# ProPrj_EasyHub_r2.net
KiCad netlist of a schematic drawn in EasyEDA Pro
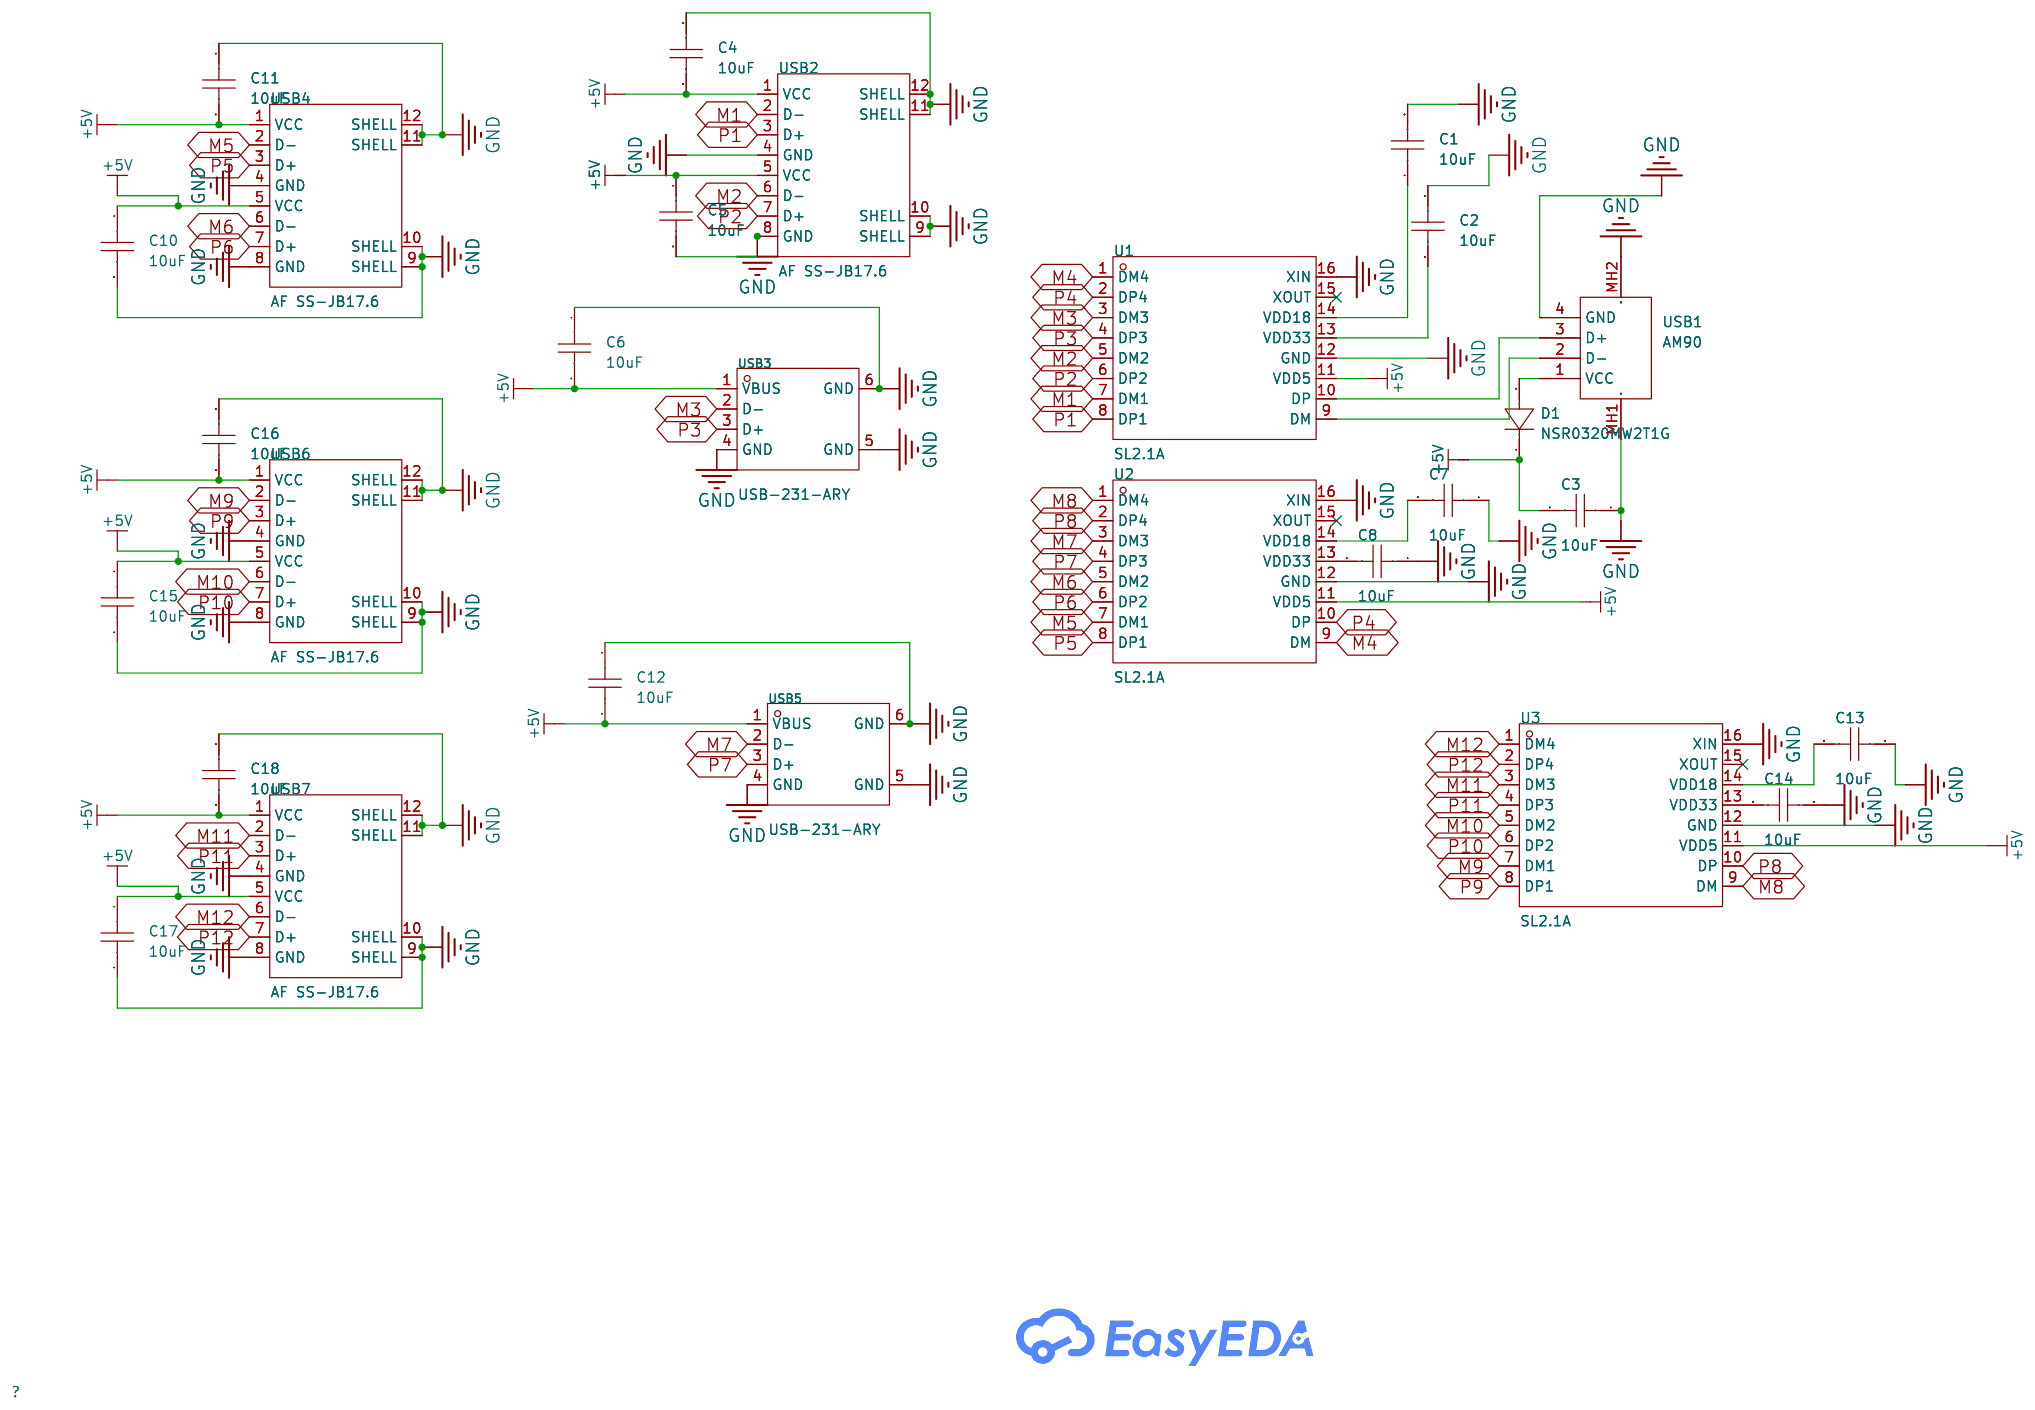
[diagram p0: schematic sheet]

(export (version "E")
  (design (tool "Eeschema 10.0.6"))
  (components
    (comp (ref "C1")
      (value "10uF")
      (footprint "easyedapro:C0603")
      (description "Capacitance:10uF Tolerance:±10% Tolerance:±10% Voltage Rating:10V Temperature Coefficient:X5R")
      (fields
        (field (name "Manufacturer Part") "CL10A106KP8NNNC")
        (field (name "Manufacturer") "SAMSUNG(三星)")
      )
      (libsource (lib "easyedapro") (part "CAP"))
    )
    (comp (ref "C2")
      (value "10uF")
      (footprint "easyedapro:C0603")
      (description "Capacitance:10uF Tolerance:±10% Tolerance:±10% Voltage Rating:10V Temperature Coefficient:X5R")
      (fields
        (field (name "Manufacturer Part") "CL10A106KP8NNNC")
        (field (name "Manufacturer") "SAMSUNG(三星)")
      )
      (libsource (lib "easyedapro") (part "CAP"))
    )
    (comp (ref "C3")
      (value "10uF")
      (footprint "easyedapro:C0603")
      (description "Capacitance:10uF Tolerance:±10% Tolerance:±10% Voltage Rating:10V Temperature Coefficient:X5R")
      (fields
        (field (name "Manufacturer Part") "CL10A106KP8NNNC")
        (field (name "Manufacturer") "SAMSUNG(三星)")
      )
      (libsource (lib "easyedapro") (part "CAP"))
    )
    (comp (ref "C4")
      (value "10uF")
      (footprint "easyedapro:C0603")
      (description "Capacitance:10uF Tolerance:±10% Tolerance:±10% Voltage Rating:10V Temperature Coefficient:X5R")
      (fields
        (field (name "Manufacturer Part") "CL10A106KP8NNNC")
        (field (name "Manufacturer") "SAMSUNG(三星)")
      )
      (libsource (lib "easyedapro") (part "CAP"))
    )
    (comp (ref "C5")
      (value "10uF")
      (footprint "easyedapro:C0603")
      (description "Capacitance:10uF Tolerance:±10% Tolerance:±10% Voltage Rating:10V Temperature Coefficient:X5R")
      (fields
        (field (name "Manufacturer Part") "CL10A106KP8NNNC")
        (field (name "Manufacturer") "SAMSUNG(三星)")
      )
      (libsource (lib "easyedapro") (part "CAP"))
    )
    (comp (ref "C6")
      (value "10uF")
      (footprint "easyedapro:C0603")
      (description "Capacitance:10uF Tolerance:±10% Tolerance:±10% Voltage Rating:10V Temperature Coefficient:X5R")
      (fields
        (field (name "Manufacturer Part") "CL10A106KP8NNNC")
        (field (name "Manufacturer") "SAMSUNG(三星)")
      )
      (libsource (lib "easyedapro") (part "CAP"))
    )
    (comp (ref "C7")
      (value "10uF")
      (footprint "easyedapro:C0603")
      (description "Capacitance:10uF Tolerance:±10% Tolerance:±10% Voltage Rating:10V Temperature Coefficient:X5R")
      (fields
        (field (name "Manufacturer Part") "CL10A106KP8NNNC")
        (field (name "Manufacturer") "SAMSUNG(三星)")
      )
      (libsource (lib "easyedapro") (part "CAP"))
    )
    (comp (ref "C8")
      (value "10uF")
      (footprint "easyedapro:C0603")
      (description "Capacitance:10uF Tolerance:±10% Tolerance:±10% Voltage Rating:10V Temperature Coefficient:X5R")
      (fields
        (field (name "Manufacturer Part") "CL10A106KP8NNNC")
        (field (name "Manufacturer") "SAMSUNG(三星)")
      )
      (libsource (lib "easyedapro") (part "CAP"))
    )
    (comp (ref "C10")
      (value "10uF")
      (footprint "easyedapro:C0603")
      (description "Capacitance:10uF Tolerance:±10% Tolerance:±10% Voltage Rating:10V Temperature Coefficient:X5R")
      (fields
        (field (name "Manufacturer Part") "CL10A106KP8NNNC")
        (field (name "Manufacturer") "SAMSUNG(三星)")
      )
      (libsource (lib "easyedapro") (part "CAP"))
    )
    (comp (ref "C11")
      (value "10uF")
      (footprint "easyedapro:C0603")
      (description "Capacitance:10uF Tolerance:±10% Tolerance:±10% Voltage Rating:10V Temperature Coefficient:X5R")
      (fields
        (field (name "Manufacturer Part") "CL10A106KP8NNNC")
        (field (name "Manufacturer") "SAMSUNG(三星)")
      )
      (libsource (lib "easyedapro") (part "CAP"))
    )
    (comp (ref "C12")
      (value "10uF")
      (footprint "easyedapro:C0603")
      (description "Capacitance:10uF Tolerance:±10% Tolerance:±10% Voltage Rating:10V Temperature Coefficient:X5R")
      (fields
        (field (name "Manufacturer Part") "CL10A106KP8NNNC")
        (field (name "Manufacturer") "SAMSUNG(三星)")
      )
      (libsource (lib "easyedapro") (part "CAP"))
    )
    (comp (ref "C13")
      (value "10uF")
      (footprint "easyedapro:C0603")
      (description "Capacitance:10uF Tolerance:±10% Tolerance:±10% Voltage Rating:10V Temperature Coefficient:X5R")
      (fields
        (field (name "Manufacturer Part") "CL10A106KP8NNNC")
        (field (name "Manufacturer") "SAMSUNG(三星)")
      )
      (libsource (lib "easyedapro") (part "CAP"))
    )
    (comp (ref "C14")
      (value "10uF")
      (footprint "easyedapro:C0603")
      (description "Capacitance:10uF Tolerance:±10% Tolerance:±10% Voltage Rating:10V Temperature Coefficient:X5R")
      (fields
        (field (name "Manufacturer Part") "CL10A106KP8NNNC")
        (field (name "Manufacturer") "SAMSUNG(三星)")
      )
      (libsource (lib "easyedapro") (part "CAP"))
    )
    (comp (ref "C15")
      (value "10uF")
      (footprint "easyedapro:C0603")
      (description "Capacitance:10uF Tolerance:±10% Tolerance:±10% Voltage Rating:10V Temperature Coefficient:X5R")
      (fields
        (field (name "Manufacturer Part") "CL10A106KP8NNNC")
        (field (name "Manufacturer") "SAMSUNG(三星)")
      )
      (libsource (lib "easyedapro") (part "CAP"))
    )
    (comp (ref "C16")
      (value "10uF")
      (footprint "easyedapro:C0603")
      (description "Capacitance:10uF Tolerance:±10% Tolerance:±10% Voltage Rating:10V Temperature Coefficient:X5R")
      (fields
        (field (name "Manufacturer Part") "CL10A106KP8NNNC")
        (field (name "Manufacturer") "SAMSUNG(三星)")
      )
      (libsource (lib "easyedapro") (part "CAP"))
    )
    (comp (ref "C17")
      (value "10uF")
      (footprint "easyedapro:C0603")
      (description "Capacitance:10uF Tolerance:±10% Tolerance:±10% Voltage Rating:10V Temperature Coefficient:X5R")
      (fields
        (field (name "Manufacturer Part") "CL10A106KP8NNNC")
        (field (name "Manufacturer") "SAMSUNG(三星)")
      )
      (libsource (lib "easyedapro") (part "CAP"))
    )
    (comp (ref "C18")
      (value "10uF")
      (footprint "easyedapro:C0603")
      (description "Capacitance:10uF Tolerance:±10% Tolerance:±10% Voltage Rating:10V Temperature Coefficient:X5R")
      (fields
        (field (name "Manufacturer Part") "CL10A106KP8NNNC")
        (field (name "Manufacturer") "SAMSUNG(三星)")
      )
      (libsource (lib "easyedapro") (part "CAP"))
    )
    (comp (ref "D1")
      (value "NSR0320MW2T1G")
      (footprint "easyedapro:SMA_L4.4-W2.8-LS5.4-RD")
      (fields (field (name "Manufacturer") "onsemi(安森美)"))
      (libsource (lib "easyedapro") (part "D_1N4007"))
    )
    (comp (ref "U1")
      (value "SL2.1A")
      (footprint "easyedapro:SOP-16_L10.0-W3.9-P1.27-LS6.0-BL")
      (fields (field (name "Manufacturer") "CoreChips(和芯润德)"))
      (libsource (lib "easyedapro") (part "SL2.1A_C6798314"))
    )
    (comp (ref "U2")
      (value "SL2.1A")
      (footprint "easyedapro:SOP-16_L10.0-W3.9-P1.27-LS6.0-BL")
      (fields (field (name "Manufacturer") "CoreChips(和芯润德)"))
      (libsource (lib "easyedapro") (part "SL2.1A_C6798314"))
    )
    (comp (ref "U3")
      (value "SL2.1A")
      (footprint "easyedapro:SOP-16_L10.0-W3.9-P1.27-LS6.0-BL")
      (fields (field (name "Manufacturer") "CoreChips(和芯润德)"))
      (libsource (lib "easyedapro") (part "SL2.1A_C6798314"))
    )
    (comp (ref "USB1")
      (value "AM90")
      (footprint "easyedapro:USB-AM-TH_AM90")
      (fields (field (name "Manufacturer") "SHOU HAN(首韩)"))
      (libsource (lib "easyedapro") (part "AM90"))
    )
    (comp (ref "USB2")
      (value "AF SS-JB17.6")
      (footprint "easyedapro:USB-A-TH_AF-SS-JB17.6")
      (fields (field (name "Manufacturer") "SHOU HAN(首韩)"))
      (libsource (lib "easyedapro") (part "AF SS-JB17.6"))
    )
    (comp (ref "USB3")
      (value "USB-231-ARY")
      (footprint "easyedapro:USB-A-TH_USB-231-ARY")
      (fields (field (name "Manufacturer") "XUNPU(讯普)"))
      (libsource (lib "easyedapro") (part "USB-231-ARY"))
    )
    (comp (ref "USB4")
      (value "AF SS-JB17.6")
      (footprint "easyedapro:USB-A-TH_AF-SS-JB17.6")
      (fields (field (name "Manufacturer") "SHOU HAN(首韩)"))
      (libsource (lib "easyedapro") (part "AF SS-JB17.6"))
    )
    (comp (ref "USB5")
      (value "USB-231-ARY")
      (footprint "easyedapro:USB-A-TH_USB-231-ARY")
      (fields (field (name "Manufacturer") "XUNPU(讯普)"))
      (libsource (lib "easyedapro") (part "USB-231-ARY"))
    )
    (comp (ref "USB6")
      (value "AF SS-JB17.6")
      (footprint "easyedapro:USB-A-TH_AF-SS-JB17.6")
      (fields (field (name "Manufacturer") "SHOU HAN(首韩)"))
      (libsource (lib "easyedapro") (part "AF SS-JB17.6"))
    )
    (comp (ref "USB7")
      (value "AF SS-JB17.6")
      (footprint "easyedapro:USB-A-TH_AF-SS-JB17.6")
      (fields (field (name "Manufacturer") "SHOU HAN(首韩)"))
      (libsource (lib "easyedapro") (part "AF SS-JB17.6"))
    )
  )
  (nets
    (net (code "1") (name "+5V") (class "Default")
      (node (ref "C10") (pin "1") (pinfunction "1_1") (pintype "input"))
      (node (ref "C11") (pin "2") (pinfunction "2_2") (pintype "input"))
      (node (ref "C12") (pin "2") (pinfunction "2_2") (pintype "input"))
      (node (ref "C15") (pin "1") (pinfunction "1_1") (pintype "input"))
      (node (ref "C16") (pin "2") (pinfunction "2_2") (pintype "input"))
      (node (ref "C17") (pin "1") (pinfunction "1_1") (pintype "input"))
      (node (ref "C18") (pin "2") (pinfunction "2_2") (pintype "input"))
      (node (ref "C3") (pin "2") (pinfunction "2_2") (pintype "input"))
      (node (ref "C4") (pin "2") (pinfunction "2_2") (pintype "input"))
      (node (ref "C5") (pin "1") (pinfunction "1_1") (pintype "input"))
      (node (ref "C6") (pin "2") (pinfunction "2_2") (pintype "input"))
      (node (ref "D1") (pin "1") (pinfunction "K_1") (pintype "input"))
      (node (ref "U1") (pin "11") (pinfunction "VDD5_11") (pintype "unspecified"))
      (node (ref "U2") (pin "11") (pinfunction "VDD5_11") (pintype "unspecified"))
      (node (ref "U3") (pin "11") (pinfunction "VDD5_11") (pintype "unspecified"))
      (node (ref "USB2") (pin "1") (pinfunction "VCC_1") (pintype "unspecified"))
      (node (ref "USB2") (pin "5") (pinfunction "VCC_5") (pintype "unspecified"))
      (node (ref "USB3") (pin "1") (pinfunction "VBUS_1") (pintype "input"))
      (node (ref "USB4") (pin "1") (pinfunction "VCC_1") (pintype "unspecified"))
      (node (ref "USB4") (pin "5") (pinfunction "VCC_5") (pintype "unspecified"))
      (node (ref "USB5") (pin "1") (pinfunction "VBUS_1") (pintype "input"))
      (node (ref "USB6") (pin "1") (pinfunction "VCC_1") (pintype "unspecified"))
      (node (ref "USB6") (pin "5") (pinfunction "VCC_5") (pintype "unspecified"))
      (node (ref "USB7") (pin "1") (pinfunction "VCC_1") (pintype "unspecified"))
      (node (ref "USB7") (pin "5") (pinfunction "VCC_5") (pintype "unspecified"))
    )
    (net (code "2") (name "GND") (class "Default")
      (node (ref "C1") (pin "2") (pinfunction "2_2") (pintype "input"))
      (node (ref "C10") (pin "2") (pinfunction "2_2") (pintype "input"))
      (node (ref "C11") (pin "1") (pinfunction "1_1") (pintype "input"))
      (node (ref "C12") (pin "1") (pinfunction "1_1") (pintype "input"))
      (node (ref "C13") (pin "1") (pinfunction "1_1") (pintype "input"))
      (node (ref "C14") (pin "1") (pinfunction "1_1") (pintype "input"))
      (node (ref "C15") (pin "2") (pinfunction "2_2") (pintype "input"))
      (node (ref "C16") (pin "1") (pinfunction "1_1") (pintype "input"))
      (node (ref "C17") (pin "2") (pinfunction "2_2") (pintype "input"))
      (node (ref "C18") (pin "1") (pinfunction "1_1") (pintype "input"))
      (node (ref "C2") (pin "1") (pinfunction "1_1") (pintype "input"))
      (node (ref "C3") (pin "1") (pinfunction "1_1") (pintype "input"))
      (node (ref "C4") (pin "1") (pinfunction "1_1") (pintype "input"))
      (node (ref "C5") (pin "2") (pinfunction "2_2") (pintype "input"))
      (node (ref "C6") (pin "1") (pinfunction "1_1") (pintype "input"))
      (node (ref "C7") (pin "1") (pinfunction "1_1") (pintype "input"))
      (node (ref "C8") (pin "1") (pinfunction "1_1") (pintype "input"))
      (node (ref "U1") (pin "12") (pinfunction "GND_12") (pintype "unspecified"))
      (node (ref "U1") (pin "16") (pinfunction "XIN_16") (pintype "unspecified"))
      (node (ref "U2") (pin "12") (pinfunction "GND_12") (pintype "unspecified"))
      (node (ref "U2") (pin "16") (pinfunction "XIN_16") (pintype "unspecified"))
      (node (ref "U3") (pin "12") (pinfunction "GND_12") (pintype "unspecified"))
      (node (ref "U3") (pin "16") (pinfunction "XIN_16") (pintype "unspecified"))
      (node (ref "USB1") (pin "4") (pinfunction "GND_4") (pintype "input"))
      (node (ref "USB1") (pin "MH1") (pinfunction "MH1_MH1") (pintype "unspecified"))
      (node (ref "USB1") (pin "MH2") (pinfunction "MH2_MH2") (pintype "unspecified"))
      (node (ref "USB2") (pin "10") (pinfunction "SHELL_10") (pintype "unspecified"))
      (node (ref "USB2") (pin "11") (pinfunction "SHELL_11") (pintype "unspecified"))
      (node (ref "USB2") (pin "12") (pinfunction "SHELL_12") (pintype "unspecified"))
      (node (ref "USB2") (pin "4") (pinfunction "GND_4") (pintype "unspecified"))
      (node (ref "USB2") (pin "8") (pinfunction "GND_8") (pintype "unspecified"))
      (node (ref "USB2") (pin "9") (pinfunction "SHELL_9") (pintype "unspecified"))
      (node (ref "USB3") (pin "4") (pinfunction "GND_4") (pintype "input"))
      (node (ref "USB3") (pin "5") (pinfunction "GND_5") (pintype "input"))
      (node (ref "USB3") (pin "6") (pinfunction "GND_6") (pintype "input"))
      (node (ref "USB4") (pin "10") (pinfunction "SHELL_10") (pintype "unspecified"))
      (node (ref "USB4") (pin "11") (pinfunction "SHELL_11") (pintype "unspecified"))
      (node (ref "USB4") (pin "12") (pinfunction "SHELL_12") (pintype "unspecified"))
      (node (ref "USB4") (pin "4") (pinfunction "GND_4") (pintype "unspecified"))
      (node (ref "USB4") (pin "8") (pinfunction "GND_8") (pintype "unspecified"))
      (node (ref "USB4") (pin "9") (pinfunction "SHELL_9") (pintype "unspecified"))
      (node (ref "USB5") (pin "4") (pinfunction "GND_4") (pintype "input"))
      (node (ref "USB5") (pin "5") (pinfunction "GND_5") (pintype "input"))
      (node (ref "USB5") (pin "6") (pinfunction "GND_6") (pintype "input"))
      (node (ref "USB6") (pin "10") (pinfunction "SHELL_10") (pintype "unspecified"))
      (node (ref "USB6") (pin "11") (pinfunction "SHELL_11") (pintype "unspecified"))
      (node (ref "USB6") (pin "12") (pinfunction "SHELL_12") (pintype "unspecified"))
      (node (ref "USB6") (pin "4") (pinfunction "GND_4") (pintype "unspecified"))
      (node (ref "USB6") (pin "8") (pinfunction "GND_8") (pintype "unspecified"))
      (node (ref "USB6") (pin "9") (pinfunction "SHELL_9") (pintype "unspecified"))
      (node (ref "USB7") (pin "10") (pinfunction "SHELL_10") (pintype "unspecified"))
      (node (ref "USB7") (pin "11") (pinfunction "SHELL_11") (pintype "unspecified"))
      (node (ref "USB7") (pin "12") (pinfunction "SHELL_12") (pintype "unspecified"))
      (node (ref "USB7") (pin "4") (pinfunction "GND_4") (pintype "unspecified"))
      (node (ref "USB7") (pin "8") (pinfunction "GND_8") (pintype "unspecified"))
      (node (ref "USB7") (pin "9") (pinfunction "SHELL_9") (pintype "unspecified"))
    )
    (net (code "3") (name "M1") (class "Default")
      (node (ref "U1") (pin "7") (pinfunction "DM1_7") (pintype "unspecified"))
      (node (ref "USB2") (pin "2") (pinfunction "D-_2") (pintype "unspecified"))
    )
    (net (code "4") (name "M2") (class "Default")
      (node (ref "U1") (pin "5") (pinfunction "DM2_5") (pintype "unspecified"))
      (node (ref "USB2") (pin "6") (pinfunction "D-_6") (pintype "unspecified"))
    )
    (net (code "5") (name "M3") (class "Default")
      (node (ref "U1") (pin "3") (pinfunction "DM3_3") (pintype "unspecified"))
      (node (ref "USB3") (pin "2") (pinfunction "D-_2") (pintype "input"))
    )
    (net (code "6") (name "M4") (class "Default")
      (node (ref "U1") (pin "1") (pinfunction "DM4_1") (pintype "unspecified"))
      (node (ref "U2") (pin "9") (pinfunction "DM_9") (pintype "unspecified"))
    )
    (net (code "7") (name "M5") (class "Default")
      (node (ref "U2") (pin "7") (pinfunction "DM1_7") (pintype "unspecified"))
      (node (ref "USB4") (pin "2") (pinfunction "D-_2") (pintype "unspecified"))
    )
    (net (code "8") (name "M6") (class "Default")
      (node (ref "U2") (pin "5") (pinfunction "DM2_5") (pintype "unspecified"))
      (node (ref "USB4") (pin "6") (pinfunction "D-_6") (pintype "unspecified"))
    )
    (net (code "9") (name "M7") (class "Default")
      (node (ref "U2") (pin "3") (pinfunction "DM3_3") (pintype "unspecified"))
      (node (ref "USB5") (pin "2") (pinfunction "D-_2") (pintype "input"))
    )
    (net (code "10") (name "M8") (class "Default")
      (node (ref "U2") (pin "1") (pinfunction "DM4_1") (pintype "unspecified"))
      (node (ref "U3") (pin "9") (pinfunction "DM_9") (pintype "unspecified"))
    )
    (net (code "11") (name "M9") (class "Default")
      (node (ref "U3") (pin "7") (pinfunction "DM1_7") (pintype "unspecified"))
      (node (ref "USB6") (pin "2") (pinfunction "D-_2") (pintype "unspecified"))
    )
    (net (code "12") (name "M10") (class "Default")
      (node (ref "U3") (pin "5") (pinfunction "DM2_5") (pintype "unspecified"))
      (node (ref "USB6") (pin "6") (pinfunction "D-_6") (pintype "unspecified"))
    )
    (net (code "13") (name "M11") (class "Default")
      (node (ref "U3") (pin "3") (pinfunction "DM3_3") (pintype "unspecified"))
      (node (ref "USB7") (pin "2") (pinfunction "D-_2") (pintype "unspecified"))
    )
    (net (code "14") (name "M12") (class "Default")
      (node (ref "U3") (pin "1") (pinfunction "DM4_1") (pintype "unspecified"))
      (node (ref "USB7") (pin "6") (pinfunction "D-_6") (pintype "unspecified"))
    )
    (net (code "15") (name "Net-(D1-A)") (class "Default")
      (node (ref "D1") (pin "2") (pinfunction "A_2") (pintype "input"))
      (node (ref "USB1") (pin "1") (pinfunction "VCC_1") (pintype "input"))
    )
    (net (code "16") (name "Net-(U1-DM)") (class "Default")
      (node (ref "U1") (pin "9") (pinfunction "DM_9") (pintype "unspecified"))
      (node (ref "USB1") (pin "2") (pinfunction "D-_2") (pintype "input"))
    )
    (net (code "17") (name "Net-(U1-DP)") (class "Default")
      (node (ref "U1") (pin "10") (pinfunction "DP_10") (pintype "unspecified"))
      (node (ref "USB1") (pin "3") (pinfunction "D+_3") (pintype "input"))
    )
    (net (code "18") (name "Net-(U1-VDD18)") (class "Default")
      (node (ref "C1") (pin "1") (pinfunction "1_1") (pintype "input"))
      (node (ref "U1") (pin "14") (pinfunction "VDD18_14") (pintype "unspecified"))
    )
    (net (code "19") (name "Net-(U1-VDD33)") (class "Default")
      (node (ref "C2") (pin "2") (pinfunction "2_2") (pintype "input"))
      (node (ref "U1") (pin "13") (pinfunction "VDD33_13") (pintype "unspecified"))
    )
    (net (code "20") (name "Net-(U2-VDD18)") (class "Default")
      (node (ref "C7") (pin "2") (pinfunction "2_2") (pintype "input"))
      (node (ref "U2") (pin "14") (pinfunction "VDD18_14") (pintype "unspecified"))
    )
    (net (code "21") (name "Net-(U2-VDD33)") (class "Default")
      (node (ref "C8") (pin "2") (pinfunction "2_2") (pintype "input"))
      (node (ref "U2") (pin "13") (pinfunction "VDD33_13") (pintype "unspecified"))
    )
    (net (code "22") (name "Net-(U3-VDD18)") (class "Default")
      (node (ref "C13") (pin "2") (pinfunction "2_2") (pintype "input"))
      (node (ref "U3") (pin "14") (pinfunction "VDD18_14") (pintype "unspecified"))
    )
    (net (code "23") (name "Net-(U3-VDD33)") (class "Default")
      (node (ref "C14") (pin "2") (pinfunction "2_2") (pintype "input"))
      (node (ref "U3") (pin "13") (pinfunction "VDD33_13") (pintype "unspecified"))
    )
    (net (code "24") (name "P1") (class "Default")
      (node (ref "U1") (pin "8") (pinfunction "DP1_8") (pintype "unspecified"))
      (node (ref "USB2") (pin "3") (pinfunction "D+_3") (pintype "unspecified"))
    )
    (net (code "25") (name "P2") (class "Default")
      (node (ref "U1") (pin "6") (pinfunction "DP2_6") (pintype "unspecified"))
      (node (ref "USB2") (pin "7") (pinfunction "D+_7") (pintype "unspecified"))
    )
    (net (code "26") (name "P3") (class "Default")
      (node (ref "U1") (pin "4") (pinfunction "DP3_4") (pintype "unspecified"))
      (node (ref "USB3") (pin "3") (pinfunction "D+_3") (pintype "input"))
    )
    (net (code "27") (name "P4") (class "Default")
      (node (ref "U1") (pin "2") (pinfunction "DP4_2") (pintype "unspecified"))
      (node (ref "U2") (pin "10") (pinfunction "DP_10") (pintype "unspecified"))
    )
    (net (code "28") (name "P5") (class "Default")
      (node (ref "U2") (pin "8") (pinfunction "DP1_8") (pintype "unspecified"))
      (node (ref "USB4") (pin "3") (pinfunction "D+_3") (pintype "unspecified"))
    )
    (net (code "29") (name "P6") (class "Default")
      (node (ref "U2") (pin "6") (pinfunction "DP2_6") (pintype "unspecified"))
      (node (ref "USB4") (pin "7") (pinfunction "D+_7") (pintype "unspecified"))
    )
    (net (code "30") (name "P7") (class "Default")
      (node (ref "U2") (pin "4") (pinfunction "DP3_4") (pintype "unspecified"))
      (node (ref "USB5") (pin "3") (pinfunction "D+_3") (pintype "input"))
    )
    (net (code "31") (name "P8") (class "Default")
      (node (ref "U2") (pin "2") (pinfunction "DP4_2") (pintype "unspecified"))
      (node (ref "U3") (pin "10") (pinfunction "DP_10") (pintype "unspecified"))
    )
    (net (code "32") (name "P9") (class "Default")
      (node (ref "U3") (pin "8") (pinfunction "DP1_8") (pintype "unspecified"))
      (node (ref "USB6") (pin "3") (pinfunction "D+_3") (pintype "unspecified"))
    )
    (net (code "33") (name "P10") (class "Default")
      (node (ref "U3") (pin "6") (pinfunction "DP2_6") (pintype "unspecified"))
      (node (ref "USB6") (pin "7") (pinfunction "D+_7") (pintype "unspecified"))
    )
    (net (code "34") (name "P11") (class "Default")
      (node (ref "U3") (pin "4") (pinfunction "DP3_4") (pintype "unspecified"))
      (node (ref "USB7") (pin "3") (pinfunction "D+_3") (pintype "unspecified"))
    )
    (net (code "35") (name "P12") (class "Default")
      (node (ref "U3") (pin "2") (pinfunction "DP4_2") (pintype "unspecified"))
      (node (ref "USB7") (pin "7") (pinfunction "D+_7") (pintype "unspecified"))
    )
    (net (code "36") (name "unconnected-(U1-XOUT-Pad15)") (class "Default")
      (node (ref "U1") (pin "15") (pinfunction "XOUT_15") (pintype "unspecified+no_connect"))
    )
    (net (code "37") (name "unconnected-(U2-XOUT-Pad15)") (class "Default")
      (node (ref "U2") (pin "15") (pinfunction "XOUT_15") (pintype "unspecified+no_connect"))
    )
    (net (code "38") (name "unconnected-(U3-XOUT-Pad15)") (class "Default")
      (node (ref "U3") (pin "15") (pinfunction "XOUT_15") (pintype "unspecified+no_connect"))
    )
  )
)
